# Arduino_Giga_R1_Qwiic_Adapter.net
KiCad netlist of a schematic drawn in EAGLE
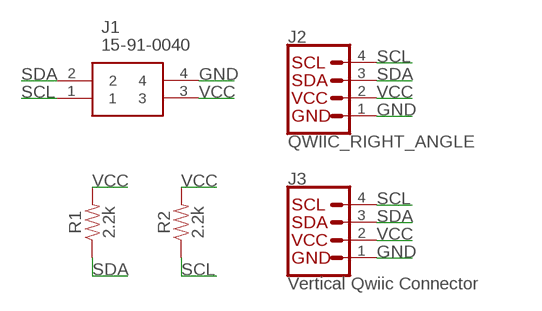
[diagram p0: schematic, sheet 1]

(export (version "E")
  (design (tool "Eeschema 10.0.6"))
  (components
    (comp (ref "J1")
      (value "15-91-0040")
      (footprint "eagle-import:15910040")
      (fields (field (name "MOUSER_PART_NUMBER") "538-15-91-0040"))
      (libsource (lib "eagle-import") (part "15-91-0040"))
    )
    (comp (ref "J2")
      (value "QWIIC_RIGHT_ANGLE")
      (footprint "eagle-import:JST04_1MM_RA")
      (libsource (lib "eagle-import") (part "QWIIC_CONNECTORJS-1MM"))
    )
    (comp (ref "J3")
      (value "Vertical Qwiic Connector")
      (footprint "eagle-import:JST04_1MM_VERT")
      (libsource (lib "eagle-import") (part "QWIIC_CONNECTOR"))
    )
    (comp (ref "R1")
      (value "2.2k")
      (footprint "eagle-import:0603")
      (libsource (lib "eagle-import") (part "2.2KOHM-0603-1/10W-1%"))
    )
    (comp (ref "R2")
      (value "2.2k")
      (footprint "eagle-import:0603")
      (libsource (lib "eagle-import") (part "2.2KOHM-0603-1/10W-1%"))
    )
  )
  (nets
    (net (code "1") (name "/GND") (class "Default")
      (node (ref "J1") (pin "4") (pinfunction "4_4") (pintype "bidirectional"))
      (node (ref "J2") (pin "1") (pinfunction "1_1") (pintype "power_in"))
      (node (ref "J3") (pin "1") (pinfunction "1_1") (pintype "power_in"))
    )
    (net (code "2") (name "/SCL") (class "Default")
      (node (ref "J1") (pin "1") (pinfunction "1_1") (pintype "bidirectional"))
      (node (ref "J2") (pin "4") (pinfunction "4_4") (pintype "passive"))
      (node (ref "J3") (pin "4") (pinfunction "4_4") (pintype "passive"))
      (node (ref "R2") (pin "1") (pinfunction "1_1") (pintype "passive"))
    )
    (net (code "3") (name "/SDA") (class "Default")
      (node (ref "J1") (pin "2") (pinfunction "2_2") (pintype "bidirectional"))
      (node (ref "J2") (pin "3") (pinfunction "3_3") (pintype "passive"))
      (node (ref "J3") (pin "3") (pinfunction "3_3") (pintype "passive"))
      (node (ref "R1") (pin "1") (pinfunction "1_1") (pintype "passive"))
    )
    (net (code "4") (name "/VCC") (class "Default")
      (node (ref "J1") (pin "3") (pinfunction "3_3") (pintype "bidirectional"))
      (node (ref "J2") (pin "2") (pinfunction "2_2") (pintype "power_in"))
      (node (ref "J3") (pin "2") (pinfunction "2_2") (pintype "power_in"))
      (node (ref "R1") (pin "2") (pinfunction "2_2") (pintype "passive"))
      (node (ref "R2") (pin "2") (pinfunction "2_2") (pintype "passive"))
    )
  )
)
